# adf5355_eval.net
KiCad netlist of a schematic drawn in EAGLE
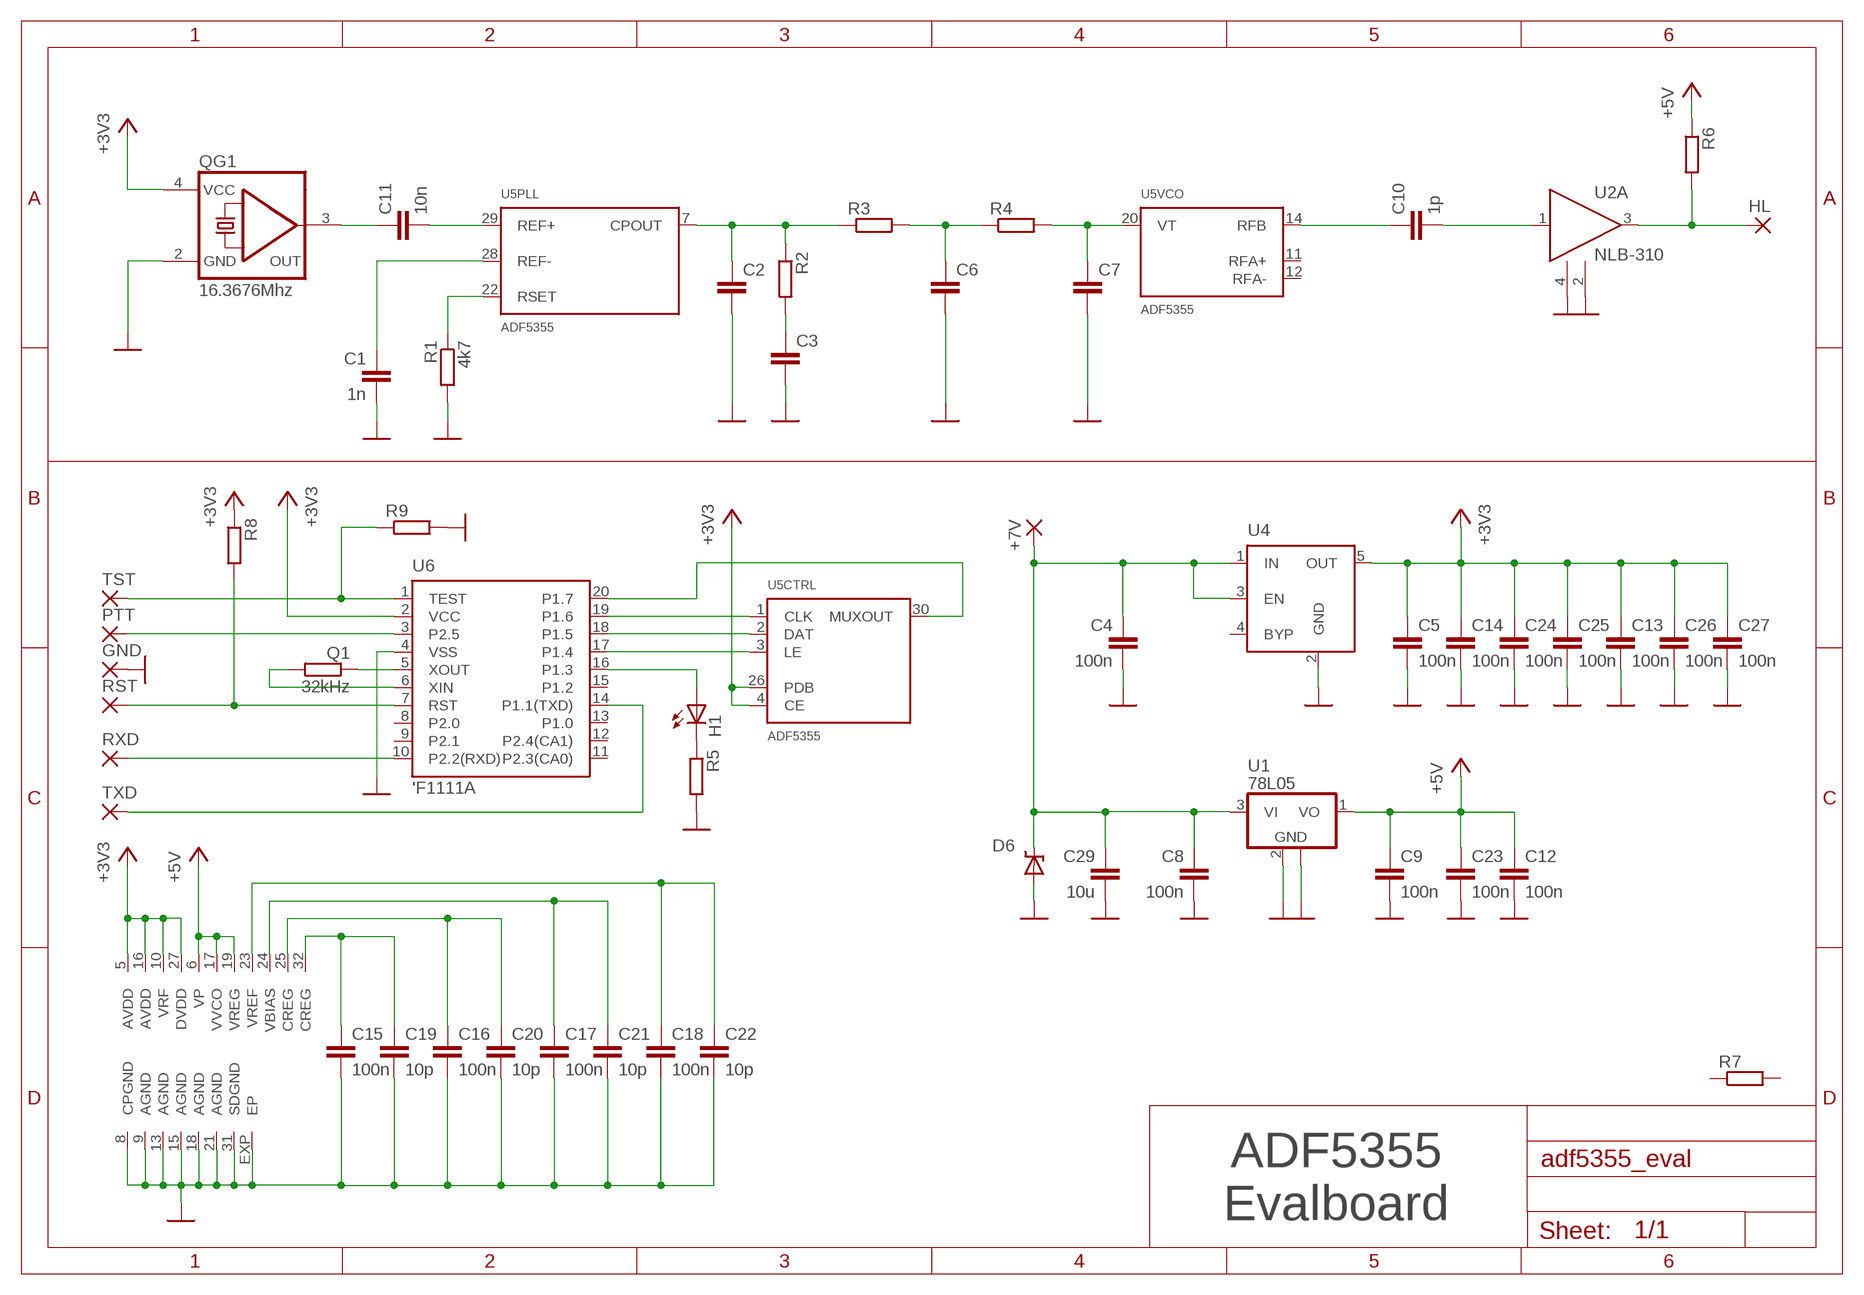
[diagram p0: schematic, sheet 1]

(export (version "E")
  (design (tool "Eeschema 10.0.6"))
  (components
    (comp (ref "+7V")
      (value "SMD2")
      (footprint "eagle-import:SMD1,27-2,54")
      (libsource (lib "eagle-import") (part "SMD2"))
    )
    (comp (ref "C1")
      (value "1n")
      (footprint "eagle-import:C0402")
      (libsource (lib "eagle-import") (part "C-EUC0402"))
    )
    (comp (ref "C2")
      (value "C-EUC0402")
      (footprint "eagle-import:C0402")
      (libsource (lib "eagle-import") (part "C-EUC0402"))
    )
    (comp (ref "C3")
      (value "C-EUC0402")
      (footprint "eagle-import:C0402")
      (libsource (lib "eagle-import") (part "C-EUC0402"))
    )
    (comp (ref "C4")
      (value "100n")
      (footprint "eagle-import:C0805")
      (libsource (lib "eagle-import") (part "C-EUC0805"))
    )
    (comp (ref "C5")
      (value "100n")
      (footprint "eagle-import:C0402")
      (libsource (lib "eagle-import") (part "C-EUC0402"))
    )
    (comp (ref "C6")
      (value "C-EUC0402")
      (footprint "eagle-import:C0402")
      (libsource (lib "eagle-import") (part "C-EUC0402"))
    )
    (comp (ref "C7")
      (value "C-EUC0402")
      (footprint "eagle-import:C0402")
      (libsource (lib "eagle-import") (part "C-EUC0402"))
    )
    (comp (ref "C8")
      (value "100n")
      (footprint "eagle-import:C0805")
      (libsource (lib "eagle-import") (part "C-EUC0805"))
    )
    (comp (ref "C9")
      (value "100n")
      (footprint "eagle-import:C0805")
      (libsource (lib "eagle-import") (part "C-EUC0805"))
    )
    (comp (ref "C10")
      (value "1p")
      (footprint "eagle-import:C0603")
      (libsource (lib "eagle-import") (part "C-EUC0603"))
    )
    (comp (ref "C11")
      (value "10n")
      (footprint "eagle-import:C0402")
      (libsource (lib "eagle-import") (part "C-EUC0402"))
    )
    (comp (ref "C12")
      (value "100n")
      (footprint "eagle-import:C0402")
      (libsource (lib "eagle-import") (part "C-EUC0402"))
    )
    (comp (ref "C13")
      (value "100n")
      (footprint "eagle-import:C0402")
      (libsource (lib "eagle-import") (part "C-EUC0402"))
    )
    (comp (ref "C14")
      (value "100n")
      (footprint "eagle-import:C0805")
      (libsource (lib "eagle-import") (part "C-EUC0805"))
    )
    (comp (ref "C15")
      (value "100n")
      (footprint "eagle-import:C0402")
      (libsource (lib "eagle-import") (part "C-EUC0402"))
    )
    (comp (ref "C16")
      (value "100n")
      (footprint "eagle-import:C0402")
      (libsource (lib "eagle-import") (part "C-EUC0402"))
    )
    (comp (ref "C17")
      (value "100n")
      (footprint "eagle-import:C0402")
      (libsource (lib "eagle-import") (part "C-EUC0402"))
    )
    (comp (ref "C18")
      (value "100n")
      (footprint "eagle-import:C0402")
      (libsource (lib "eagle-import") (part "C-EUC0402"))
    )
    (comp (ref "C19")
      (value "10p")
      (footprint "eagle-import:C0402")
      (libsource (lib "eagle-import") (part "C-EUC0402"))
    )
    (comp (ref "C20")
      (value "10p")
      (footprint "eagle-import:C0402")
      (libsource (lib "eagle-import") (part "C-EUC0402"))
    )
    (comp (ref "C21")
      (value "10p")
      (footprint "eagle-import:C0402")
      (libsource (lib "eagle-import") (part "C-EUC0402"))
    )
    (comp (ref "C22")
      (value "10p")
      (footprint "eagle-import:C0402")
      (libsource (lib "eagle-import") (part "C-EUC0402"))
    )
    (comp (ref "C23")
      (value "100n")
      (footprint "eagle-import:C0603")
      (libsource (lib "eagle-import") (part "C-EUC0603"))
    )
    (comp (ref "C24")
      (value "100n")
      (footprint "eagle-import:C0805")
      (libsource (lib "eagle-import") (part "C-EUC0805"))
    )
    (comp (ref "C25")
      (value "100n")
      (footprint "eagle-import:C0402")
      (libsource (lib "eagle-import") (part "C-EUC0402"))
    )
    (comp (ref "C26")
      (value "100n")
      (footprint "eagle-import:C0402")
      (libsource (lib "eagle-import") (part "C-EUC0402"))
    )
    (comp (ref "C27")
      (value "100n")
      (footprint "eagle-import:C0402")
      (libsource (lib "eagle-import") (part "C-EUC0402"))
    )
    (comp (ref "C29")
      (value "10u")
      (footprint "eagle-import:C0805")
      (libsource (lib "eagle-import") (part "C-EUC0805"))
    )
    (comp (ref "D6")
      (value "SUPPRESSOR-SMBJ")
      (footprint "eagle-import:SMBJ")
      (libsource (lib "eagle-import") (part "SUPPRESSOR-SMBJ"))
    )
    (comp (ref "GND")
      (value "SMD2")
      (footprint "eagle-import:SMD1,27-2,54")
      (libsource (lib "eagle-import") (part "SMD2"))
    )
    (comp (ref "H1")
      (value "PL006-WCR12")
      (footprint "eagle-import:SOT23")
      (libsource (lib "eagle-import") (part "PL006-WCR12"))
    )
    (comp (ref "HL")
      (value "1,6/0,9")
      (footprint "eagle-import:1,6_0,9")
      (libsource (lib "eagle-import") (part "1,6/0,9"))
    )
    (comp (ref "PTT")
      (value "SMD2")
      (footprint "eagle-import:SMD1,27-2,54")
      (libsource (lib "eagle-import") (part "SMD2"))
    )
    (comp (ref "Q1")
      (value "32kHz")
      (footprint "eagle-import:R1206")
      (libsource (lib "eagle-import") (part "R-EU_R1206"))
    )
    (comp (ref "QG1")
      (value "16.3676Mhz")
      (footprint "eagle-import:CTS406")
      (libsource (lib "eagle-import") (part "XO"))
    )
    (comp (ref "R1")
      (value "4k7")
      (footprint "eagle-import:R0402")
      (libsource (lib "eagle-import") (part "R-EU_R0402"))
    )
    (comp (ref "R2")
      (value "R-EU_R0402")
      (footprint "eagle-import:R0402")
      (libsource (lib "eagle-import") (part "R-EU_R0402"))
    )
    (comp (ref "R3")
      (value "R-EU_R0402")
      (footprint "eagle-import:R0402")
      (libsource (lib "eagle-import") (part "R-EU_R0402"))
    )
    (comp (ref "R4")
      (value "R-EU_R0402")
      (footprint "eagle-import:R0402")
      (libsource (lib "eagle-import") (part "R-EU_R0402"))
    )
    (comp (ref "R5")
      (value "R-EU_R0603")
      (footprint "eagle-import:R0603")
      (libsource (lib "eagle-import") (part "R-EU_R0603"))
    )
    (comp (ref "R6")
      (value "R-EU_R0603")
      (footprint "eagle-import:R0603")
      (libsource (lib "eagle-import") (part "R-EU_R0603"))
    )
    (comp (ref "R7")
      (value "R-EU_R0402")
      (footprint "eagle-import:R0402")
      (libsource (lib "eagle-import") (part "R-EU_R0402"))
    )
    (comp (ref "R8")
      (value "R-EU_R0402")
      (footprint "eagle-import:R0402")
      (libsource (lib "eagle-import") (part "R-EU_R0402"))
    )
    (comp (ref "R9")
      (value "R-EU_R0402")
      (footprint "eagle-import:R0402")
      (libsource (lib "eagle-import") (part "R-EU_R0402"))
    )
    (comp (ref "RST")
      (value "SMD2")
      (footprint "eagle-import:SMD1,27-2,54")
      (libsource (lib "eagle-import") (part "SMD2"))
    )
    (comp (ref "RXD")
      (value "SMD2")
      (footprint "eagle-import:SMD1,27-2,54")
      (libsource (lib "eagle-import") (part "SMD2"))
    )
    (comp (ref "TST")
      (value "SMD2")
      (footprint "eagle-import:SMD1,27-2,54")
      (libsource (lib "eagle-import") (part "SMD2"))
    )
    (comp (ref "TXD")
      (value "SMD2")
      (footprint "eagle-import:SMD1,27-2,54")
      (libsource (lib "eagle-import") (part "SMD2"))
    )
    (comp (ref "U1")
      (value "78L05")
      (footprint "eagle-import:SOT89")
      (libsource (lib "eagle-import") (part "78LF05"))
    )
    (comp (ref "U2")
      (value "NLB-310")
      (footprint "eagle-import:WW107")
      (libsource (lib "eagle-import") (part "ERA"))
    )
    (comp (ref "U4")
      (value "MIC5219XX")
      (footprint "eagle-import:SOT23-5")
      (libsource (lib "eagle-import") (part "MIC5219XX"))
    )
    (comp (ref "U5")
      (value "ADF5355")
      (footprint "eagle-import:LFCSP32")
      (libsource (lib "eagle-import") (part "ADF5355"))
    )
    (comp (ref "U6")
      (value "'F1111A")
      (footprint "eagle-import:PW20")
      (libsource (lib "eagle-import") (part "F11X1A---PW20"))
    )
  )
  (nets
    (net (code "1") (name "+3V3") (class "Default")
      (node (ref "C13") (pin "1") (pinfunction "1_1") (pintype "passive"))
      (node (ref "C14") (pin "1") (pinfunction "1_1") (pintype "passive"))
      (node (ref "C24") (pin "1") (pinfunction "1_1") (pintype "passive"))
      (node (ref "C25") (pin "1") (pinfunction "1_1") (pintype "passive"))
      (node (ref "C26") (pin "1") (pinfunction "1_1") (pintype "passive"))
      (node (ref "C27") (pin "1") (pinfunction "1_1") (pintype "passive"))
      (node (ref "C5") (pin "1") (pinfunction "1_1") (pintype "passive"))
      (node (ref "QG1") (pin "4") (pinfunction "VCC_4") (pintype "power_in"))
      (node (ref "R8") (pin "1") (pinfunction "1_1") (pintype "passive"))
      (node (ref "U4") (pin "5") (pinfunction "OUT_5") (pintype "output"))
      (node (ref "U5") (pin "10") (pinfunction "VRF_10") (pintype "power_in"))
      (node (ref "U5") (pin "16") (pinfunction "AVDD_16") (pintype "power_in"))
      (node (ref "U5") (pin "26") (pinfunction "PDB_26") (pintype "input"))
      (node (ref "U5") (pin "27") (pinfunction "DVDD_27") (pintype "power_in"))
      (node (ref "U5") (pin "4") (pinfunction "CE_4") (pintype "input"))
      (node (ref "U5") (pin "5") (pinfunction "AVDD_5") (pintype "power_in"))
      (node (ref "U6") (pin "2") (pinfunction "VCC_2") (pintype "power_in"))
    )
    (net (code "2") (name "+5V") (class "Default")
      (node (ref "C12") (pin "1") (pinfunction "1_1") (pintype "passive"))
      (node (ref "C23") (pin "1") (pinfunction "1_1") (pintype "passive"))
      (node (ref "C9") (pin "1") (pinfunction "1_1") (pintype "passive"))
      (node (ref "R6") (pin "1") (pinfunction "1_1") (pintype "passive"))
      (node (ref "U1") (pin "1") (pinfunction "VO_1") (pintype "passive"))
      (node (ref "U5") (pin "17") (pinfunction "VVCO_17") (pintype "power_in"))
      (node (ref "U5") (pin "19") (pinfunction "VREG_19") (pintype "power_in"))
      (node (ref "U5") (pin "6") (pinfunction "VP_6") (pintype "power_in"))
    )
    (net (code "3") (name "GND") (class "Default")
      (node (ref "C1") (pin "2") (pinfunction "2_2") (pintype "passive"))
      (node (ref "C12") (pin "2") (pinfunction "2_2") (pintype "passive"))
      (node (ref "C13") (pin "2") (pinfunction "2_2") (pintype "passive"))
      (node (ref "C14") (pin "2") (pinfunction "2_2") (pintype "passive"))
      (node (ref "C15") (pin "2") (pinfunction "2_2") (pintype "passive"))
      (node (ref "C16") (pin "2") (pinfunction "2_2") (pintype "passive"))
      (node (ref "C17") (pin "2") (pinfunction "2_2") (pintype "passive"))
      (node (ref "C18") (pin "2") (pinfunction "2_2") (pintype "passive"))
      (node (ref "C19") (pin "2") (pinfunction "2_2") (pintype "passive"))
      (node (ref "C2") (pin "2") (pinfunction "2_2") (pintype "passive"))
      (node (ref "C20") (pin "2") (pinfunction "2_2") (pintype "passive"))
      (node (ref "C21") (pin "2") (pinfunction "2_2") (pintype "passive"))
      (node (ref "C22") (pin "2") (pinfunction "2_2") (pintype "passive"))
      (node (ref "C23") (pin "2") (pinfunction "2_2") (pintype "passive"))
      (node (ref "C24") (pin "2") (pinfunction "2_2") (pintype "passive"))
      (node (ref "C25") (pin "2") (pinfunction "2_2") (pintype "passive"))
      (node (ref "C26") (pin "2") (pinfunction "2_2") (pintype "passive"))
      (node (ref "C27") (pin "2") (pinfunction "2_2") (pintype "passive"))
      (node (ref "C29") (pin "2") (pinfunction "2_2") (pintype "passive"))
      (node (ref "C3") (pin "2") (pinfunction "2_2") (pintype "passive"))
      (node (ref "C4") (pin "2") (pinfunction "2_2") (pintype "passive"))
      (node (ref "C5") (pin "2") (pinfunction "2_2") (pintype "passive"))
      (node (ref "C6") (pin "2") (pinfunction "2_2") (pintype "passive"))
      (node (ref "C7") (pin "2") (pinfunction "2_2") (pintype "passive"))
      (node (ref "C8") (pin "2") (pinfunction "2_2") (pintype "passive"))
      (node (ref "C9") (pin "2") (pinfunction "2_2") (pintype "passive"))
      (node (ref "D6") (pin "A") (pinfunction "A_A") (pintype "passive"))
      (node (ref "GND") (pin "1") (pinfunction "P_1") (pintype "passive"))
      (node (ref "QG1") (pin "2") (pinfunction "GND_2") (pintype "power_in"))
      (node (ref "R1") (pin "2") (pinfunction "2_2") (pintype "passive"))
      (node (ref "R5") (pin "2") (pinfunction "2_2") (pintype "passive"))
      (node (ref "R9") (pin "2") (pinfunction "2_2") (pintype "passive"))
      (node (ref "U1") (pin "2") (pinfunction "GND_2") (pintype "passive"))
      (node (ref "U1") (pin "2@1") (pinfunction "GND_2@1") (pintype "passive"))
      (node (ref "U2") (pin "2") (pinfunction "GND_2") (pintype "power_in"))
      (node (ref "U2") (pin "4") (pinfunction "GND_4") (pintype "power_in"))
      (node (ref "U4") (pin "2") (pinfunction "GND_2") (pintype "power_in"))
      (node (ref "U5") (pin "13") (pinfunction "AGND_13") (pintype "power_in"))
      (node (ref "U5") (pin "15") (pinfunction "AGND_15") (pintype "power_in"))
      (node (ref "U5") (pin "18") (pinfunction "AGND_18") (pintype "power_in"))
      (node (ref "U5") (pin "21") (pinfunction "AGND_21") (pintype "power_in"))
      (node (ref "U5") (pin "31") (pinfunction "SDGND_31") (pintype "power_in"))
      (node (ref "U5") (pin "8") (pinfunction "CPGND_8") (pintype "power_in"))
      (node (ref "U5") (pin "9") (pinfunction "AGND_9") (pintype "power_in"))
      (node (ref "U5") (pin "EXP") (pinfunction "EP_EXP") (pintype "power_in"))
      (node (ref "U6") (pin "4") (pinfunction "VSS_4") (pintype "power_in"))
    )
    (net (code "4") (name "Net-(+7V-P)") (class "Default")
      (node (ref "+7V") (pin "1") (pinfunction "P_1") (pintype "passive"))
      (node (ref "C29") (pin "1") (pinfunction "1_1") (pintype "passive"))
      (node (ref "C4") (pin "1") (pinfunction "1_1") (pintype "passive"))
      (node (ref "C8") (pin "1") (pinfunction "1_1") (pintype "passive"))
      (node (ref "D6") (pin "C") (pinfunction "C_C") (pintype "passive"))
      (node (ref "U1") (pin "3") (pinfunction "VI_3") (pintype "input"))
      (node (ref "U4") (pin "1") (pinfunction "IN_1") (pintype "input"))
      (node (ref "U4") (pin "3") (pinfunction "EN_3") (pintype "input"))
    )
    (net (code "5") (name "Net-(C3-Pad1)") (class "Default")
      (node (ref "C3") (pin "1") (pinfunction "1_1") (pintype "passive"))
      (node (ref "R2") (pin "2") (pinfunction "2_2") (pintype "passive"))
    )
    (net (code "6") (name "Net-(C6-Pad1)") (class "Default")
      (node (ref "C6") (pin "1") (pinfunction "1_1") (pintype "passive"))
      (node (ref "R3") (pin "2") (pinfunction "2_2") (pintype "passive"))
      (node (ref "R4") (pin "1") (pinfunction "1_1") (pintype "passive"))
    )
    (net (code "7") (name "Net-(C15-Pad1)") (class "Default")
      (node (ref "C15") (pin "1") (pinfunction "1_1") (pintype "passive"))
      (node (ref "C19") (pin "1") (pinfunction "1_1") (pintype "passive"))
      (node (ref "U5") (pin "32") (pinfunction "CREG_32") (pintype "power_in"))
    )
    (net (code "8") (name "Net-(C16-Pad1)") (class "Default")
      (node (ref "C16") (pin "1") (pinfunction "1_1") (pintype "passive"))
      (node (ref "C20") (pin "1") (pinfunction "1_1") (pintype "passive"))
      (node (ref "U5") (pin "25") (pinfunction "CREG_25") (pintype "power_in"))
    )
    (net (code "9") (name "Net-(H1-A)") (class "Default")
      (node (ref "H1") (pin "1") (pinfunction "A_1") (pintype "passive"))
      (node (ref "U6") (pin "16") (pinfunction "P1.3_16") (pintype "bidirectional"))
    )
    (net (code "10") (name "Net-(H1-C)") (class "Default")
      (node (ref "H1") (pin "3") (pinfunction "C_3") (pintype "passive"))
      (node (ref "R5") (pin "1") (pinfunction "1_1") (pintype "passive"))
    )
    (net (code "11") (name "Net-(HL-P)") (class "Default")
      (node (ref "HL") (pin "1") (pinfunction "P_1") (pintype "passive"))
      (node (ref "R6") (pin "2") (pinfunction "2_2") (pintype "passive"))
      (node (ref "U2") (pin "3") (pinfunction "OUT_3") (pintype "output"))
    )
    (net (code "12") (name "Net-(PTT-P)") (class "Default")
      (node (ref "PTT") (pin "1") (pinfunction "P_1") (pintype "passive"))
      (node (ref "U6") (pin "3") (pinfunction "P2.5_3") (pintype "bidirectional"))
    )
    (net (code "13") (name "Net-(QG1-OUT)") (class "Default")
      (node (ref "C11") (pin "1") (pinfunction "1_1") (pintype "passive"))
      (node (ref "QG1") (pin "3") (pinfunction "OUT_3") (pintype "output"))
    )
    (net (code "14") (name "Net-(RST-P)") (class "Default")
      (node (ref "R8") (pin "2") (pinfunction "2_2") (pintype "passive"))
      (node (ref "RST") (pin "1") (pinfunction "P_1") (pintype "passive"))
      (node (ref "U6") (pin "7") (pinfunction "RST_7") (pintype "input"))
    )
    (net (code "15") (name "Net-(RXD-P)") (class "Default")
      (node (ref "RXD") (pin "1") (pinfunction "P_1") (pintype "passive"))
      (node (ref "U6") (pin "10") (pinfunction "P2.2(RXD)_10") (pintype "bidirectional"))
    )
    (net (code "16") (name "Net-(TST-P)") (class "Default")
      (node (ref "R9") (pin "1") (pinfunction "1_1") (pintype "passive"))
      (node (ref "TST") (pin "1") (pinfunction "P_1") (pintype "passive"))
      (node (ref "U6") (pin "1") (pinfunction "TEST_1") (pintype "input"))
    )
    (net (code "17") (name "Net-(TXD-P)") (class "Default")
      (node (ref "TXD") (pin "1") (pinfunction "P_1") (pintype "passive"))
      (node (ref "U6") (pin "14") (pinfunction "P1.1(TXD)_14") (pintype "bidirectional"))
    )
    (net (code "18") (name "Net-(U2A-IN)") (class "Default")
      (node (ref "C10") (pin "2") (pinfunction "2_2") (pintype "passive"))
      (node (ref "U2") (pin "1") (pinfunction "IN_1") (pintype "input"))
    )
    (net (code "19") (name "Net-(U5A-CLK)") (class "Default")
      (node (ref "U5") (pin "1") (pinfunction "CLK_1") (pintype "input"))
      (node (ref "U6") (pin "19") (pinfunction "P1.6_19") (pintype "bidirectional"))
    )
    (net (code "20") (name "Net-(U5A-DAT)") (class "Default")
      (node (ref "U5") (pin "2") (pinfunction "DAT_2") (pintype "input"))
      (node (ref "U6") (pin "18") (pinfunction "P1.5_18") (pintype "bidirectional"))
    )
    (net (code "21") (name "Net-(U5A-LE)") (class "Default")
      (node (ref "U5") (pin "3") (pinfunction "LE_3") (pintype "input"))
      (node (ref "U6") (pin "17") (pinfunction "P1.4_17") (pintype "bidirectional"))
    )
    (net (code "22") (name "Net-(U5A-MUXOUT)") (class "Default")
      (node (ref "U5") (pin "30") (pinfunction "MUXOUT_30") (pintype "input"))
      (node (ref "U6") (pin "20") (pinfunction "P1.7_20") (pintype "bidirectional"))
    )
    (net (code "23") (name "Net-(U5B-CPOUT)") (class "Default")
      (node (ref "C2") (pin "1") (pinfunction "1_1") (pintype "passive"))
      (node (ref "R2") (pin "1") (pinfunction "1_1") (pintype "passive"))
      (node (ref "R3") (pin "1") (pinfunction "1_1") (pintype "passive"))
      (node (ref "U5") (pin "7") (pinfunction "CPOUT_7") (pintype "output"))
    )
    (net (code "24") (name "Net-(U5B-REF+)") (class "Default")
      (node (ref "C11") (pin "2") (pinfunction "2_2") (pintype "passive"))
      (node (ref "U5") (pin "29") (pinfunction "REF+_29") (pintype "input"))
    )
    (net (code "25") (name "Net-(U5B-REF-)") (class "Default")
      (node (ref "C1") (pin "1") (pinfunction "1_1") (pintype "passive"))
      (node (ref "U5") (pin "28") (pinfunction "REF-_28") (pintype "input"))
    )
    (net (code "26") (name "Net-(U5B-RSET)") (class "Default")
      (node (ref "R1") (pin "1") (pinfunction "1_1") (pintype "passive"))
      (node (ref "U5") (pin "22") (pinfunction "RSET_22") (pintype "passive"))
    )
    (net (code "27") (name "Net-(U5C-VBIAS)") (class "Default")
      (node (ref "C17") (pin "1") (pinfunction "1_1") (pintype "passive"))
      (node (ref "C21") (pin "1") (pinfunction "1_1") (pintype "passive"))
      (node (ref "U5") (pin "24") (pinfunction "VBIAS_24") (pintype "power_in"))
    )
    (net (code "28") (name "Net-(U5C-VREF)") (class "Default")
      (node (ref "C18") (pin "1") (pinfunction "1_1") (pintype "passive"))
      (node (ref "C22") (pin "1") (pinfunction "1_1") (pintype "passive"))
      (node (ref "U5") (pin "23") (pinfunction "VREF_23") (pintype "power_in"))
    )
    (net (code "29") (name "Net-(U5D-RFB)") (class "Default")
      (node (ref "C10") (pin "1") (pinfunction "1_1") (pintype "passive"))
      (node (ref "U5") (pin "14") (pinfunction "RFB_14") (pintype "output"))
    )
    (net (code "30") (name "Net-(U5D-VT)") (class "Default")
      (node (ref "C7") (pin "1") (pinfunction "1_1") (pintype "passive"))
      (node (ref "R4") (pin "2") (pinfunction "2_2") (pintype "passive"))
      (node (ref "U5") (pin "20") (pinfunction "VT_20") (pintype "input"))
    )
    (net (code "31") (name "Net-(U6-XIN)") (class "Default")
      (node (ref "Q1") (pin "2") (pinfunction "2_2") (pintype "passive"))
      (node (ref "U6") (pin "6") (pinfunction "XIN_6") (pintype "input"))
    )
    (net (code "32") (name "Net-(U6-XOUT)") (class "Default")
      (node (ref "Q1") (pin "1") (pinfunction "1_1") (pintype "passive"))
      (node (ref "U6") (pin "5") (pinfunction "XOUT_5") (pintype "output"))
    )
    (net (code "33") (name "unconnected-(R7-Pad1)") (class "Default")
      (node (ref "R7") (pin "1") (pinfunction "1_1") (pintype "passive"))
    )
    (net (code "34") (name "unconnected-(R7-Pad2)") (class "Default")
      (node (ref "R7") (pin "2") (pinfunction "2_2") (pintype "passive"))
    )
    (net (code "35") (name "unconnected-(U4-BYP-Pad4)") (class "Default")
      (node (ref "U4") (pin "4") (pinfunction "BYP_4") (pintype "passive"))
    )
    (net (code "36") (name "unconnected-(U5D-RFA+-Pad11)") (class "Default")
      (node (ref "U5") (pin "11") (pinfunction "RFA+_11") (pintype "output"))
    )
    (net (code "37") (name "unconnected-(U5D-RFA--Pad12)") (class "Default")
      (node (ref "U5") (pin "12") (pinfunction "RFA-_12") (pintype "output"))
    )
    (net (code "38") (name "unconnected-(U6-P1.0-Pad13)") (class "Default")
      (node (ref "U6") (pin "13") (pinfunction "P1.0_13") (pintype "bidirectional"))
    )
    (net (code "39") (name "unconnected-(U6-P1.2-Pad15)") (class "Default")
      (node (ref "U6") (pin "15") (pinfunction "P1.2_15") (pintype "bidirectional"))
    )
    (net (code "40") (name "unconnected-(U6-P2.0-Pad8)") (class "Default")
      (node (ref "U6") (pin "8") (pinfunction "P2.0_8") (pintype "bidirectional"))
    )
    (net (code "41") (name "unconnected-(U6-P2.1-Pad9)") (class "Default")
      (node (ref "U6") (pin "9") (pinfunction "P2.1_9") (pintype "bidirectional"))
    )
    (net (code "42") (name "unconnected-(U6-P2.3(CA0)-Pad11)") (class "Default")
      (node (ref "U6") (pin "11") (pinfunction "P2.3(CA0)_11") (pintype "bidirectional"))
    )
    (net (code "43") (name "unconnected-(U6-P2.4(CA1)-Pad12)") (class "Default")
      (node (ref "U6") (pin "12") (pinfunction "P2.4(CA1)_12") (pintype "bidirectional"))
    )
  )
)
